# Active_filter.net
KiCad netlist of a schematic drawn in Altium Designer
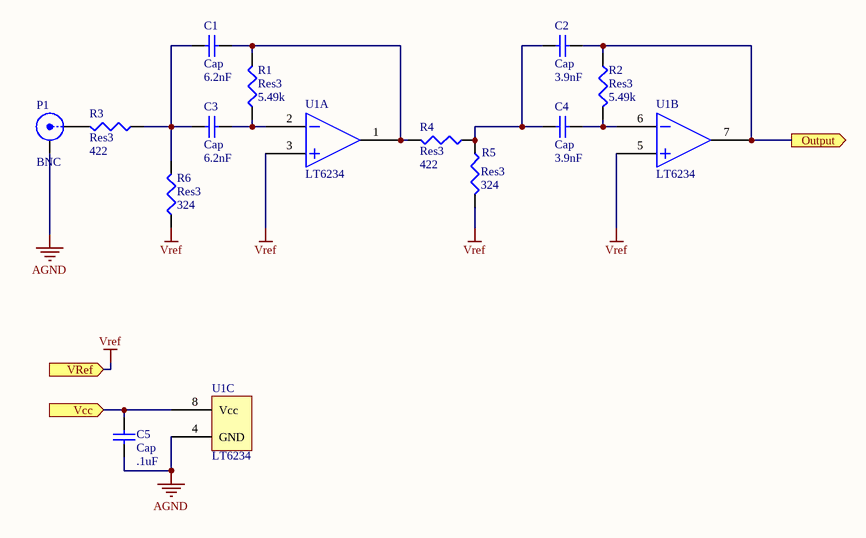
[diagram p0: Active_filter.SchDoc]

(export (version "E")
  (design (tool "Eeschema 10.0.6"))
  (components
    (comp (ref "C1")
      (value "Cap")
      (footprint "1608[0603]")
      (description "Capacitor")
      (fields (field (name "ALTIUM_VALUE") "6.2nF") (field (name "PUBLISHER") "Altium Limited"))
      (libsource (lib "Miscellaneous Devices") (part "Cap"))
    )
    (comp (ref "C2")
      (value "Cap")
      (footprint "1608[0603]")
      (description "Capacitor")
      (fields (field (name "ALTIUM_VALUE") "3.9nF") (field (name "PUBLISHER") "Altium Limited"))
      (libsource (lib "Miscellaneous Devices") (part "Cap"))
    )
    (comp (ref "C3")
      (value "Cap")
      (footprint "1608[0603]")
      (description "Capacitor")
      (fields (field (name "ALTIUM_VALUE") "6.2nF") (field (name "PUBLISHER") "Altium Limited"))
      (libsource (lib "Miscellaneous Devices") (part "Cap"))
    )
    (comp (ref "C4")
      (value "Cap")
      (footprint "1608[0603]")
      (description "Capacitor")
      (fields (field (name "ALTIUM_VALUE") "3.9nF") (field (name "PUBLISHER") "Altium Limited"))
      (libsource (lib "Miscellaneous Devices") (part "Cap"))
    )
    (comp (ref "C5")
      (value "Cap")
      (footprint "1608[0603]")
      (description "Capacitor")
      (fields (field (name "ALTIUM_VALUE") ".1uF") (field (name "PUBLISHER") "Altium Limited"))
      (libsource (lib "Miscellaneous Devices") (part "Cap"))
    )
    (comp (ref "P1")
      (value "BNC")
      (footprint "BNC_RA CON")
      (description "BNC Elbow Connector")
      (fields (field (name "PUBLISHER") "Altium Limited"))
      (libsource (lib "Miscellaneous Connectors") (part "BNC"))
    )
    (comp (ref "R1")
      (value "Res3")
      (footprint "1608[0603]")
      (description "Resistor")
      (fields (field (name "ALTIUM_VALUE") "5.49k") (field (name "PUBLISHER") "Altium Limited"))
      (libsource (lib "Miscellaneous Devices") (part "Res3"))
    )
    (comp (ref "R2")
      (value "Res3")
      (footprint "J1-0603")
      (description "Resistor")
      (fields (field (name "ALTIUM_VALUE") "5.49k") (field (name "PUBLISHER") "Altium Limited"))
      (libsource (lib "Miscellaneous Devices") (part "Res3"))
    )
    (comp (ref "R3")
      (value "Res3")
      (footprint "1608[0603]")
      (description "Resistor")
      (fields (field (name "ALTIUM_VALUE") "422") (field (name "PUBLISHER") "Altium Limited"))
      (libsource (lib "Miscellaneous Devices") (part "Res3"))
    )
    (comp (ref "R4")
      (value "Res3")
      (footprint "J1-0603")
      (description "Resistor")
      (fields (field (name "ALTIUM_VALUE") "422") (field (name "PUBLISHER") "Altium Limited"))
      (libsource (lib "Miscellaneous Devices") (part "Res3"))
    )
    (comp (ref "R5")
      (value "Res3")
      (footprint "J1-0603")
      (description "Resistor")
      (fields (field (name "ALTIUM_VALUE") "324") (field (name "PUBLISHER") "Altium Limited"))
      (libsource (lib "Miscellaneous Devices") (part "Res3"))
    )
    (comp (ref "R6")
      (value "Res3")
      (footprint "1608[0603]")
      (description "Resistor")
      (fields (field (name "ALTIUM_VALUE") "324") (field (name "PUBLISHER") "Altium Limited"))
      (libsource (lib "Miscellaneous Devices") (part "Res3"))
    )
    (comp (ref "U1")
      (value "LT6234")
      (footprint "SOIC127P600X150-8N(LT6233)")
      (libsource (lib "OpAmpLib") (part "LT6234"))
    )
  )
  (nets
    (net (code "1") (name "/Output") (class "Default")
      (node (ref "C2") (pin "2") (pinfunction "2_2") (pintype "passive"))
      (node (ref "R2") (pin "1") (pinfunction "1_1") (pintype "passive"))
      (node (ref "U1") (pin "7") (pinfunction "OUT_B_7") (pintype "passive"))
    )
    (net (code "2") (name "/Vcc") (class "Default")
      (node (ref "C5") (pin "2") (pinfunction "2_2") (pintype "passive"))
      (node (ref "U1") (pin "8") (pinfunction "Vcc_8") (pintype "passive"))
    )
    (net (code "3") (name "AGND") (class "Default")
      (node (ref "C5") (pin "1") (pinfunction "1_1") (pintype "passive"))
      (node (ref "P1") (pin "2") (pinfunction "Y_2") (pintype "passive"))
      (node (ref "U1") (pin "4") (pinfunction "GND_4") (pintype "passive"))
    )
    (net (code "4") (name "Net-(C1-Pad1)") (class "Default")
      (node (ref "C1") (pin "1") (pinfunction "1_1") (pintype "passive"))
      (node (ref "C3") (pin "1") (pinfunction "1_1") (pintype "passive"))
      (node (ref "R3") (pin "1") (pinfunction "1_1") (pintype "passive"))
      (node (ref "R6") (pin "2") (pinfunction "2_2") (pintype "passive"))
    )
    (net (code "5") (name "Net-(C2-Pad1)") (class "Default")
      (node (ref "C2") (pin "1") (pinfunction "1_1") (pintype "passive"))
      (node (ref "C4") (pin "2") (pinfunction "2_2") (pintype "passive"))
      (node (ref "R4") (pin "1") (pinfunction "1_1") (pintype "passive"))
      (node (ref "R5") (pin "1") (pinfunction "1_1") (pintype "passive"))
    )
    (net (code "6") (name "Net-(P1-X)") (class "Default")
      (node (ref "P1") (pin "1") (pinfunction "X_1") (pintype "passive"))
      (node (ref "R3") (pin "2") (pinfunction "2_2") (pintype "passive"))
    )
    (net (code "7") (name "Net-(U1A--IN_A)") (class "Default")
      (node (ref "C3") (pin "2") (pinfunction "2_2") (pintype "passive"))
      (node (ref "R1") (pin "1") (pinfunction "1_1") (pintype "passive"))
      (node (ref "U1") (pin "2") (pinfunction "-IN_A_2") (pintype "passive"))
    )
    (net (code "8") (name "Net-(U1A-OUT_A)") (class "Default")
      (node (ref "C1") (pin "2") (pinfunction "2_2") (pintype "passive"))
      (node (ref "R1") (pin "2") (pinfunction "2_2") (pintype "passive"))
      (node (ref "R4") (pin "2") (pinfunction "2_2") (pintype "passive"))
      (node (ref "U1") (pin "1") (pinfunction "OUT_A_1") (pintype "passive"))
    )
    (net (code "9") (name "Net-(U1B--IN_B)") (class "Default")
      (node (ref "C4") (pin "1") (pinfunction "1_1") (pintype "passive"))
      (node (ref "R2") (pin "2") (pinfunction "2_2") (pintype "passive"))
      (node (ref "U1") (pin "6") (pinfunction "-IN_B_6") (pintype "passive"))
    )
    (net (code "10") (name "Vref") (class "Default")
      (node (ref "R5") (pin "2") (pinfunction "2_2") (pintype "passive"))
      (node (ref "R6") (pin "1") (pinfunction "1_1") (pintype "passive"))
      (node (ref "U1") (pin "3") (pinfunction "+IN_A_3") (pintype "passive"))
      (node (ref "U1") (pin "5") (pinfunction "+IN_B_5") (pintype "passive"))
    )
  )
)
